# fonte.net
KiCad netlist of a schematic drawn in EAGLE
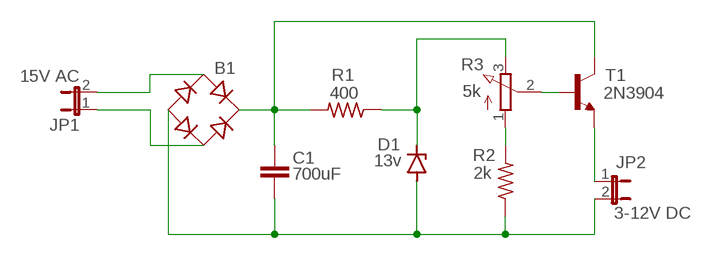
[diagram p0: schematic, sheet 1]

(export (version "E")
  (design (tool "Eeschema 10.0.6"))
  (components
    (comp (ref "B1")
      (value "B-DIL")
      (footprint "eagle-import:B-DIL")
      (libsource (lib "eagle-import") (part "B-DIL"))
    )
    (comp (ref "C1")
      (value "700uF")
      (footprint "eagle-import:C025-025X050")
      (libsource (lib "eagle-import") (part "C-EU025-025X050"))
    )
    (comp (ref "D1")
      (value "13v")
      (footprint "eagle-import:SOD81")
      (libsource (lib "eagle-import") (part "BZD23"))
    )
    (comp (ref "JP1")
      (value "15V AC")
      (footprint "eagle-import:JP1")
      (libsource (lib "eagle-import") (part "JP1E"))
    )
    (comp (ref "JP2")
      (value "3-12V DC")
      (footprint "eagle-import:JP1")
      (libsource (lib "eagle-import") (part "JP1E"))
    )
    (comp (ref "R1")
      (value "400")
      (footprint "eagle-import:0204_7")
      (libsource (lib "eagle-import") (part "R-US_0204/7"))
    )
    (comp (ref "R2")
      (value "2k")
      (footprint "eagle-import:0204_7")
      (libsource (lib "eagle-import") (part "R-US_0204/7"))
    )
    (comp (ref "R3")
      (value "5k")
      (footprint "eagle-import:3RP_1610N")
      (libsource (lib "eagle-import") (part "3RP/1610N"))
    )
    (comp (ref "T1")
      (value "2N3904")
      (footprint "eagle-import:TO92")
      (libsource (lib "eagle-import") (part "2N3904"))
    )
  )
  (nets
    (net (code "1") (name "Net-(B1-Pad-)") (class "Default")
      (node (ref "B1") (pin "-") (pinfunction "-_-") (pintype "passive"))
      (node (ref "C1") (pin "2") (pinfunction "2_2") (pintype "passive"))
      (node (ref "D1") (pin "A") (pinfunction "A_A") (pintype "passive"))
      (node (ref "JP2") (pin "2") (pinfunction "2_2") (pintype "passive"))
      (node (ref "R2") (pin "1") (pinfunction "1_1") (pintype "passive"))
    )
    (net (code "2") (name "Net-(B1-PadAC1)") (class "Default")
      (node (ref "B1") (pin "AC1") (pinfunction "AC1_AC1") (pintype "passive"))
      (node (ref "JP1") (pin "2") (pinfunction "2_2") (pintype "passive"))
    )
    (net (code "3") (name "Net-(B1-PadAC2)") (class "Default")
      (node (ref "B1") (pin "AC2") (pinfunction "AC2_AC2") (pintype "passive"))
      (node (ref "JP1") (pin "1") (pinfunction "1_1") (pintype "passive"))
    )
    (net (code "4") (name "Net-(R3-A)") (class "Default")
      (node (ref "R2") (pin "2") (pinfunction "2_2") (pintype "passive"))
      (node (ref "R3") (pin "1") (pinfunction "A_1") (pintype "passive"))
    )
    (net (code "5") (name "Net-(R3-E)") (class "Default")
      (node (ref "D1") (pin "C") (pinfunction "C_C") (pintype "passive"))
      (node (ref "R1") (pin "1") (pinfunction "1_1") (pintype "passive"))
      (node (ref "R3") (pin "3") (pinfunction "E_3") (pintype "passive"))
    )
    (net (code "6") (name "Net-(R3-S)") (class "Default")
      (node (ref "R3") (pin "2") (pinfunction "S_2") (pintype "passive"))
      (node (ref "T1") (pin "2") (pinfunction "B_2") (pintype "passive"))
    )
    (net (code "7") (name "Net-(T1-C)") (class "Default")
      (node (ref "B1") (pin "+") (pinfunction "+_+") (pintype "passive"))
      (node (ref "C1") (pin "1") (pinfunction "1_1") (pintype "passive"))
      (node (ref "R1") (pin "2") (pinfunction "2_2") (pintype "passive"))
      (node (ref "T1") (pin "1") (pinfunction "C_1") (pintype "passive"))
    )
    (net (code "8") (name "Net-(T1-E)") (class "Default")
      (node (ref "JP2") (pin "1") (pinfunction "1_1") (pintype "passive"))
      (node (ref "T1") (pin "3") (pinfunction "E_3") (pintype "passive"))
    )
  )
)
